# indicator.net
KiCad netlist of a schematic drawn in Altium Designer
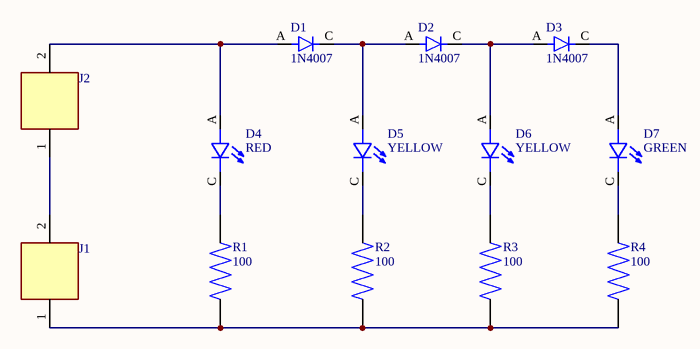
[diagram p0: indicator.SchDoc]

(export (version "E")
  (design (tool "Eeschema 10.0.6"))
  (components
    (comp (ref "D1")
      (value "1N4007")
      (footprint "DIOAD1060W80L520D270")
      (description "Diode Switching 1KV 1A 2-Pin DO-41")
      (libsource (lib "1N4007") (part "1N4007"))
    )
    (comp (ref "D2")
      (value "1N4007")
      (footprint "DIOAD1060W80L520D270")
      (description "Diode Switching 1KV 1A 2-Pin DO-41")
      (libsource (lib "1N4007") (part "1N4007"))
    )
    (comp (ref "D3")
      (value "1N4007")
      (footprint "DIOAD1060W80L520D270")
      (description "Diode Switching 1KV 1A 2-Pin DO-41")
      (libsource (lib "1N4007") (part "1N4007"))
    )
    (comp (ref "D4")
      (value "RED")
      (footprint "LEDRD254W57D500H1070:LEDRD254W57D500H1070")
      (description "LED, Orange, Through Hole, T-1 3/4 (5mm), 30 mA, 2.1 V, 635 nm")
      (fields (field (name "MP") "L08R5000Q1"))
      (libsource (lib "L08R5000Q1") (part "L08R5000Q1"))
    )
    (comp (ref "D5")
      (value "YELLOW")
      (footprint "LEDRD254W57D500H1070:LEDRD254W57D500H1070")
      (description "LED, Orange, Through Hole, T-1 3/4 (5mm), 30 mA, 2.1 V, 635 nm")
      (fields (field (name "MP") "L08R5000Q1"))
      (libsource (lib "L08R5000Q1") (part "L08R5000Q1"))
    )
    (comp (ref "D6")
      (value "YELLOW")
      (footprint "LEDRD254W57D500H1070:LEDRD254W57D500H1070")
      (description "LED, Orange, Through Hole, T-1 3/4 (5mm), 30 mA, 2.1 V, 635 nm")
      (fields (field (name "MP") "L08R5000Q1"))
      (libsource (lib "L08R5000Q1") (part "L08R5000Q1"))
    )
    (comp (ref "D7")
      (value "GREEN")
      (footprint "LEDRD254W57D500H1070:LEDRD254W57D500H1070")
      (description "LED, Orange, Through Hole, T-1 3/4 (5mm), 30 mA, 2.1 V, 635 nm")
      (fields (field (name "MP") "L08R5000Q1"))
      (libsource (lib "L08R5000Q1") (part "L08R5000Q1"))
    )
    (comp (ref "J1")
      (value "64900221122")
      (footprint "64900221122")
      (description "Connector Header Through Hole 2 position")
      (fields (field (name "MF") "Wurth Electronics"))
      (libsource (lib "SnapEDAsch") (part "64900221122"))
    )
    (comp (ref "J2")
      (value "64900221122")
      (footprint "64900221122")
      (description "Connector Header Through Hole 2 position")
      (fields (field (name "MF") "Wurth Electronics"))
      (libsource (lib "SnapEDAsch") (part "64900221122"))
    )
    (comp (ref "R1")
      (value "100")
      (footprint "RESAD1100W55L680D260")
      (description "Through Hole Resistor Axial - Metal Film")
      (fields (field (name "MF") "Yageo") (field (name "MP") "MFR-25FBF52-1K"))
      (libsource (lib "MFR-25FBF52-1K") (part "MFR-25FBF52-1K"))
    )
    (comp (ref "R2")
      (value "100")
      (footprint "RESAD1100W55L680D260")
      (description "Through Hole Resistor Axial - Metal Film")
      (fields (field (name "MF") "Yageo") (field (name "MP") "MFR-25FBF52-1K"))
      (libsource (lib "MFR-25FBF52-1K") (part "MFR-25FBF52-1K"))
    )
    (comp (ref "R3")
      (value "100")
      (footprint "RESAD1100W55L680D260")
      (description "Through Hole Resistor Axial - Metal Film")
      (fields (field (name "MF") "Yageo") (field (name "MP") "MFR-25FBF52-1K"))
      (libsource (lib "MFR-25FBF52-1K") (part "MFR-25FBF52-1K"))
    )
    (comp (ref "R4")
      (value "100")
      (footprint "RESAD1100W55L680D260")
      (description "1.78 kOhms Â±1% 0.25W, 1/4W Through Hole Resistor Axial - Metal Film")
      (fields (field (name "MF") "Yageo") (field (name "MP") "MFR-25FBF52-1K"))
      (libsource (lib "MFR-25FBF52-1K") (part "MFR-25FBF52-1K"))
    )
  )
  (nets
    (net (code "1") (name "Net-(D1-PadA)") (class "Default")
      (node (ref "D1") (pin "A") (pinfunction "A_A") (pintype "passive"))
      (node (ref "D4") (pin "A") (pinfunction "A_A") (pintype "passive"))
      (node (ref "J2") (pin "2") (pinfunction "2_2") (pintype "passive"))
    )
    (net (code "2") (name "Net-(D1-PadC)") (class "Default")
      (node (ref "D1") (pin "C") (pinfunction "C_C") (pintype "passive"))
      (node (ref "D2") (pin "A") (pinfunction "A_A") (pintype "passive"))
      (node (ref "D5") (pin "A") (pinfunction "A_A") (pintype "passive"))
    )
    (net (code "3") (name "Net-(D2-PadC)") (class "Default")
      (node (ref "D2") (pin "C") (pinfunction "C_C") (pintype "passive"))
      (node (ref "D3") (pin "A") (pinfunction "A_A") (pintype "passive"))
      (node (ref "D6") (pin "A") (pinfunction "A_A") (pintype "passive"))
    )
    (net (code "4") (name "Net-(D3-PadC)") (class "Default")
      (node (ref "D3") (pin "C") (pinfunction "C_C") (pintype "passive"))
      (node (ref "D7") (pin "A") (pinfunction "A_A") (pintype "passive"))
    )
    (net (code "5") (name "Net-(D4-PadC)") (class "Default")
      (node (ref "D4") (pin "C") (pinfunction "C_C") (pintype "passive"))
      (node (ref "R1") (pin "2") (pinfunction "2_2") (pintype "passive"))
    )
    (net (code "6") (name "Net-(D5-PadC)") (class "Default")
      (node (ref "D5") (pin "C") (pinfunction "C_C") (pintype "passive"))
      (node (ref "R2") (pin "2") (pinfunction "2_2") (pintype "passive"))
    )
    (net (code "7") (name "Net-(D6-PadC)") (class "Default")
      (node (ref "D6") (pin "C") (pinfunction "C_C") (pintype "passive"))
      (node (ref "R3") (pin "1") (pinfunction "1_1") (pintype "passive"))
    )
    (net (code "8") (name "Net-(D7-PadC)") (class "Default")
      (node (ref "D7") (pin "C") (pinfunction "C_C") (pintype "passive"))
      (node (ref "R4") (pin "1") (pinfunction "1_1") (pintype "passive"))
    )
    (net (code "9") (name "Net-(J1-Pad1)") (class "Default")
      (node (ref "J1") (pin "1") (pinfunction "1_1") (pintype "passive"))
      (node (ref "R1") (pin "1") (pinfunction "1_1") (pintype "passive"))
      (node (ref "R2") (pin "1") (pinfunction "1_1") (pintype "passive"))
      (node (ref "R3") (pin "2") (pinfunction "2_2") (pintype "passive"))
      (node (ref "R4") (pin "2") (pinfunction "2_2") (pintype "passive"))
    )
    (net (code "10") (name "Net-(J1-Pad2)") (class "Default")
      (node (ref "J1") (pin "2") (pinfunction "2_2") (pintype "passive"))
      (node (ref "J2") (pin "1") (pinfunction "1_1") (pintype "passive"))
    )
  )
)
